# Potentiometer.net
KiCad netlist of a schematic drawn in Altium Designer
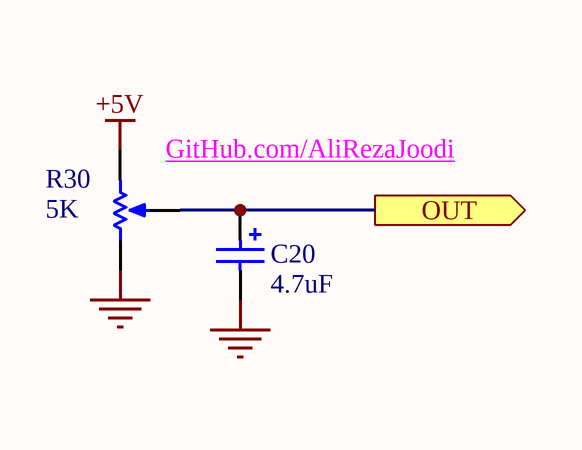
[diagram p0: Potentiometer.SchDoc]

(export (version "E")
  (design (tool "Eeschema 10.0.6"))
  (components
    (comp (ref "C20")
      (value "4.7uF")
      (footprint "CAPPR2.5-6.3x5")
      (description "Polarized Capacitor (Radial)")
      (fields
        (field (name "MANUFACTURER") "Generic Components")
        (field (name "Comment") "C18")
        (field (name "PUBLISHER") "Altium Limited")
      )
      (libsource (lib "Miscellaneous Devices") (part "Cap Pol1"))
    )
    (comp (ref "R30")
      (value "5K")
      (footprint "VR4_")
      (description "Potentiometer")
      (fields
        (field (name "MANUFACTURER") "Generic Components")
        (field (name "Comment") "POT")
        (field (name "PUBLISHER") "Altium Limited")
      )
      (libsource (lib "my Libraries") (part "RPot1"))
    )
  )
  (nets
    (net (code "1") (name "+5V") (class "Default")
      (node (ref "R30") (pin "2") (pinfunction "BOT_2") (pintype "passive"))
    )
    (net (code "2") (name "/OUT") (class "Default")
      (node (ref "C20") (pin "1") (pinfunction "1_1") (pintype "passive"))
      (node (ref "R30") (pin "3") (pinfunction "TAP_3") (pintype "passive"))
    )
    (net (code "3") (name "GND") (class "Default")
      (node (ref "C20") (pin "2") (pinfunction "2_2") (pintype "passive"))
      (node (ref "R30") (pin "1") (pinfunction "TOP_1") (pintype "passive"))
    )
  )
)
